# design.net
KiCad netlist of a schematic drawn in Altium Designer
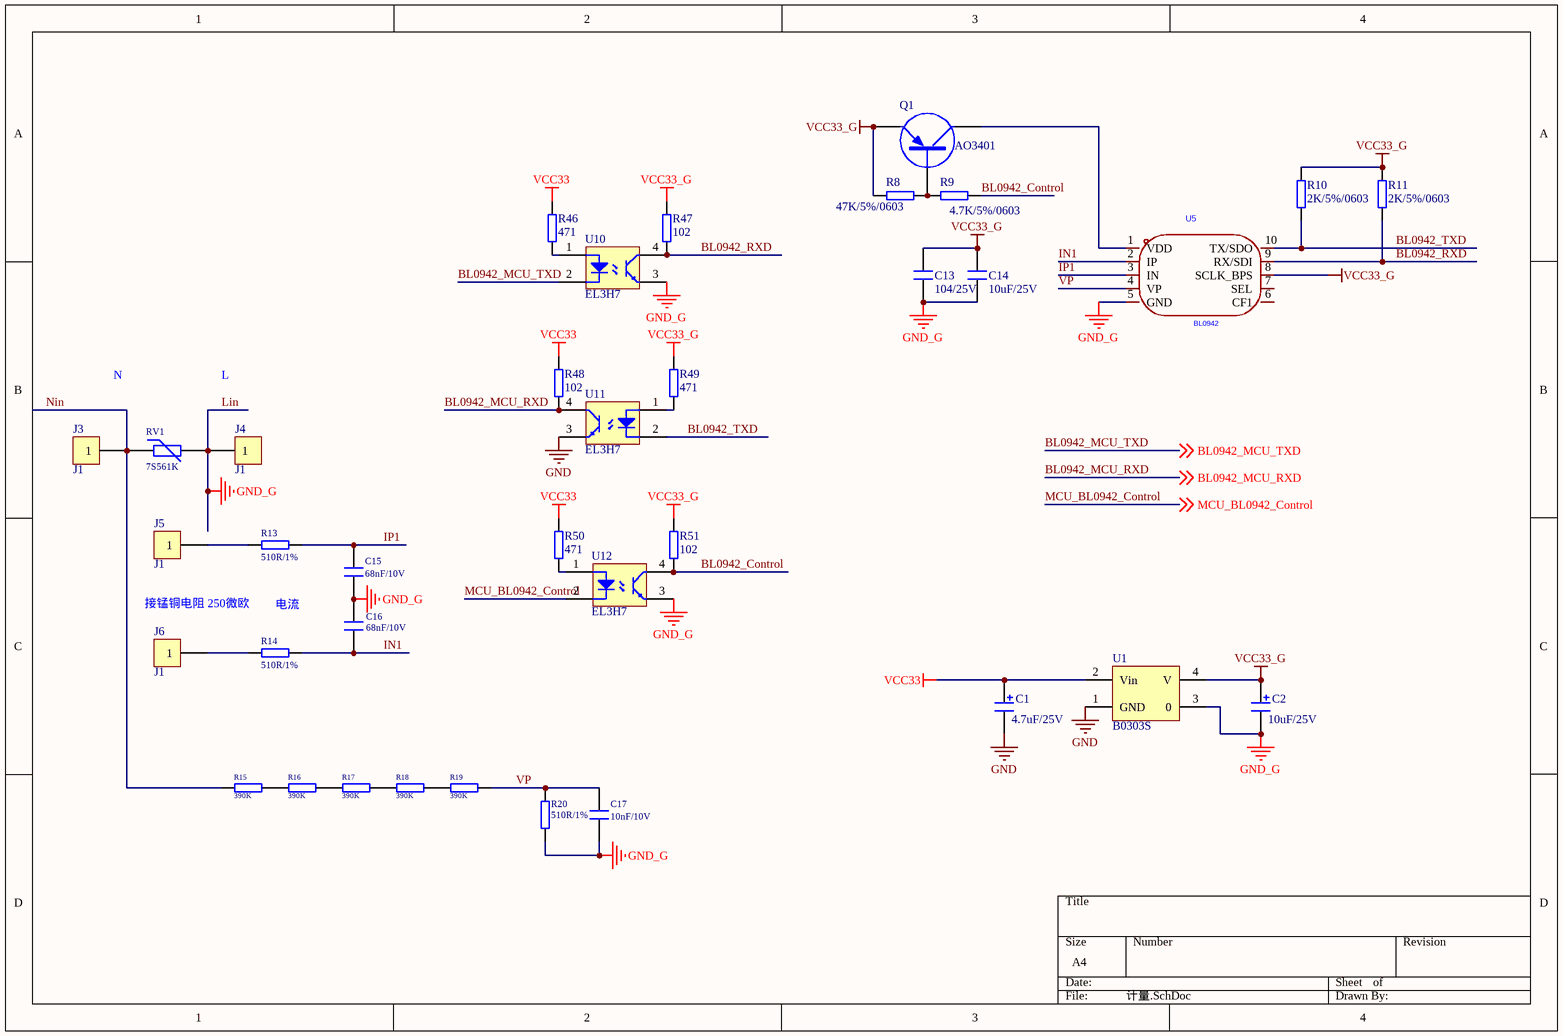
[diagram p0: 计量.SchDoc]

(export (version "E")
  (design (tool "Eeschema 10.0.6"))
  (components
    (comp (ref "C1") (value "4.7uF/25V") (footprint "0805R") (libsource (lib "ES_Schematic") (part "CAP+")))
    (comp (ref "C2") (value "10uF/25V") (footprint "0805R") (libsource (lib "ES_Schematic") (part "CAP+")))
    (comp (ref "C13") (value "104/25V") (footprint "0603R") (libsource (lib "ES_Schematic") (part "CAP_1")))
    (comp (ref "C14") (value "10uF/25V") (footprint "0603R") (libsource (lib "ES_Schematic") (part "CAP_1")))
    (comp (ref "C15") (value "68nF/10V") (footprint "0603R") (libsource (lib "ES_Schematic") (part "CAP")))
    (comp (ref "C16") (value "68nF/10V") (footprint "0603R") (libsource (lib "ES_Schematic") (part "CAP")))
    (comp (ref "C17") (value "10nF/10V") (footprint "0603R") (libsource (lib "ES_Schematic") (part "CAP")))
    (comp (ref "J3") (value "J1") (footprint "贴片焊盘V1（3*2椭圆）") (libsource (lib "ES_Schematic") (part "J1")))
    (comp (ref "J4") (value "J1") (footprint "贴片焊盘V1（3*2椭圆）") (libsource (lib "") (part "J1_1")))
    (comp (ref "J5") (value "J1") (footprint "贴片焊盘V1（3*2椭圆）") (libsource (lib "ES_Schematic") (part "J1")))
    (comp (ref "J6") (value "J1") (footprint "贴片焊盘V1（3*2椭圆）") (libsource (lib "ES_Schematic") (part "J1")))
    (comp (ref "Q1") (value "AO3401") (footprint "SOT-23") (libsource (lib "ES_Schematic") (part "PNP")))
    (comp (ref "R8") (value "47K/5%/0603") (footprint "0603R") (libsource (lib "ES_Schematic") (part "RES")))
    (comp (ref "R9") (value "4.7K/5%/0603") (footprint "0603R") (libsource (lib "ES_Schematic") (part "RES")))
    (comp (ref "R10") (value "2K/5%/0603") (footprint "0603R") (libsource (lib "ES_Schematic") (part "RES")))
    (comp (ref "R11") (value "2K/5%/0603") (footprint "0603R") (libsource (lib "ES_Schematic") (part "RES")))
    (comp (ref "R13") (value "510R/1%") (footprint "0603R") (libsource (lib "ES_Schematic") (part "RES")))
    (comp (ref "R14") (value "510R/1%") (footprint "0603R") (libsource (lib "ES_Schematic") (part "RES")))
    (comp (ref "R15") (value "390K") (footprint "0805R") (libsource (lib "ES_Schematic") (part "RES")))
    (comp (ref "R16") (value "390K") (footprint "0805R") (libsource (lib "ES_Schematic") (part "RES")))
    (comp (ref "R17") (value "390K") (footprint "0805R") (libsource (lib "ES_Schematic") (part "RES")))
    (comp (ref "R18") (value "390K") (footprint "0805R") (libsource (lib "ES_Schematic") (part "RES")))
    (comp (ref "R19") (value "390K") (footprint "0805R") (libsource (lib "ES_Schematic") (part "RES")))
    (comp (ref "R20") (value "510R/1%") (footprint "0603R") (libsource (lib "ES_Schematic") (part "RES")))
    (comp (ref "R46") (value "471") (footprint "0603R") (libsource (lib "ES_Schematic") (part "RES")))
    (comp (ref "R47") (value "102") (footprint "0603R") (libsource (lib "ES_Schematic") (part "RES")))
    (comp (ref "R48") (value "102") (footprint "0603R") (libsource (lib "ES_Schematic") (part "RES")))
    (comp (ref "R49") (value "471") (footprint "0603R") (libsource (lib "ES_Schematic") (part "RES")))
    (comp (ref "R50") (value "471") (footprint "0603R") (libsource (lib "ES_Schematic") (part "RES")))
    (comp (ref "R51") (value "102") (footprint "0603R") (libsource (lib "ES_Schematic") (part "RES")))
    (comp (ref "RV1")
      (value "7S561K")
      (footprint "10D821K")
      (description "Varistor (Voltage-Sensitive Resistor)")
      (fields (field (name "PUBLISHER") "Altium Limited"))
      (libsource (lib "Miscellaneous Devices") (part "Res Varistor"))
    )
    (comp (ref "U1") (value "B0303S") (footprint "B1205S-1WR3") (libsource (lib "sangjian") (part "B0505S")))
    (comp (ref "U5")
      (value "BL0942")
      (footprint "BL0942-10pin")
      (fields (field (name "MANUFACTURER") "BL(上海贝岭)"))
      (libsource (lib "altium-import") (part "root_0_BL0942_C2837510_"))
    )
    (comp (ref "U10")
      (value "EL3H7")
      (footprint "EL3H7")
      (libsource (lib "ES_Schematic") (part "Optical_Coupler_1"))
    )
    (comp (ref "U11") (value "EL3H7") (footprint "EL3H7") (libsource (lib "") (part "Optical_Coupler_1_1")))
    (comp (ref "U12")
      (value "EL3H7")
      (footprint "EL3H7")
      (libsource (lib "ES_Schematic") (part "Optical_Coupler_1"))
    )
  )
  (nets
    (net (code "1") (name "/BL0942_Control") (class "Default")
      (node (ref "R51") (pin "1") (pinfunction "1_1") (pintype "passive"))
      (node (ref "R9") (pin "2") (pinfunction "2_2") (pintype "passive"))
      (node (ref "U12") (pin "4") (pinfunction "C_4") (pintype "passive"))
    )
    (net (code "2") (name "/BL0942_RXD") (class "Default")
      (node (ref "R11") (pin "1") (pinfunction "1_1") (pintype "passive"))
      (node (ref "R47") (pin "1") (pinfunction "1_1") (pintype "passive"))
      (node (ref "U10") (pin "4") (pinfunction "C_4") (pintype "passive"))
      (node (ref "U5") (pin "9") (pinfunction "RX/SDI_9") (pintype "passive"))
    )
    (net (code "3") (name "/BL0942_TXD") (class "Default")
      (node (ref "R10") (pin "1") (pinfunction "1_1") (pintype "passive"))
      (node (ref "U11") (pin "2") (pinfunction "K_2") (pintype "passive"))
      (node (ref "U5") (pin "10") (pinfunction "TX/SDO_10") (pintype "passive"))
    )
    (net (code "4") (name "/IN1") (class "Default")
      (node (ref "C16") (pin "1") (pinfunction "1_1") (pintype "passive"))
      (node (ref "R14") (pin "2") (pinfunction "2_2") (pintype "passive"))
      (node (ref "U5") (pin "2") (pinfunction "IP_2") (pintype "passive"))
    )
    (net (code "5") (name "/IP1") (class "Default")
      (node (ref "C15") (pin "1") (pinfunction "1_1") (pintype "passive"))
      (node (ref "R13") (pin "2") (pinfunction "2_2") (pintype "passive"))
      (node (ref "U5") (pin "3") (pinfunction "IN_3") (pintype "passive"))
    )
    (net (code "6") (name "/Nin") (class "Default")
      (node (ref "J3") (pin "1") (pinfunction "1_1") (pintype "passive"))
      (node (ref "R15") (pin "2") (pinfunction "2_2") (pintype "passive"))
      (node (ref "RV1") (pin "1") (pinfunction "1_1") (pintype "passive"))
    )
    (net (code "7") (name "/VP") (class "Default")
      (node (ref "C17") (pin "1") (pinfunction "1_1") (pintype "passive"))
      (node (ref "R19") (pin "1") (pinfunction "1_1") (pintype "passive"))
      (node (ref "R20") (pin "2") (pinfunction "2_2") (pintype "passive"))
      (node (ref "U5") (pin "4") (pinfunction "VP_4") (pintype "passive"))
    )
    (net (code "8") (name "BL0942_MCU_RXD") (class "Default")
      (node (ref "R48") (pin "1") (pinfunction "1_1") (pintype "passive"))
      (node (ref "U11") (pin "4") (pinfunction "C_4") (pintype "passive"))
    )
    (net (code "9") (name "BL0942_MCU_TXD") (class "Default")
      (node (ref "U10") (pin "2") (pinfunction "K_2") (pintype "passive"))
    )
    (net (code "10") (name "GND") (class "Default")
      (node (ref "C1") (pin "2") (pinfunction "2_2") (pintype "passive"))
      (node (ref "U1") (pin "1") (pinfunction "GND_1") (pintype "passive"))
      (node (ref "U11") (pin "3") (pinfunction "E_3") (pintype "passive"))
    )
    (net (code "11") (name "GND_G") (class "Default")
      (node (ref "C13") (pin "1") (pinfunction "1_1") (pintype "passive"))
      (node (ref "C14") (pin "1") (pinfunction "1_1") (pintype "passive"))
      (node (ref "C15") (pin "2") (pinfunction "2_2") (pintype "passive"))
      (node (ref "C16") (pin "2") (pinfunction "2_2") (pintype "passive"))
      (node (ref "C17") (pin "2") (pinfunction "2_2") (pintype "passive"))
      (node (ref "C2") (pin "2") (pinfunction "2_2") (pintype "passive"))
      (node (ref "J4") (pin "1") (pinfunction "1_1") (pintype "passive"))
      (node (ref "R20") (pin "1") (pinfunction "1_1") (pintype "passive"))
      (node (ref "RV1") (pin "2") (pinfunction "2_2") (pintype "passive"))
      (node (ref "U1") (pin "3") (pinfunction "0_3") (pintype "passive"))
      (node (ref "U10") (pin "3") (pinfunction "E_3") (pintype "passive"))
      (node (ref "U12") (pin "3") (pinfunction "E_3") (pintype "passive"))
      (node (ref "U5") (pin "5") (pinfunction "GND_5") (pintype "passive"))
    )
    (net (code "12") (name "MCU_BL0942_Control") (class "Default")
      (node (ref "U12") (pin "2") (pinfunction "K_2") (pintype "passive"))
    )
    (net (code "13") (name "Net-(J5-Pad1)") (class "Default")
      (node (ref "J5") (pin "1") (pinfunction "1_1") (pintype "passive"))
      (node (ref "R13") (pin "1") (pinfunction "1_1") (pintype "passive"))
    )
    (net (code "14") (name "Net-(J6-Pad1)") (class "Default")
      (node (ref "J6") (pin "1") (pinfunction "1_1") (pintype "passive"))
      (node (ref "R14") (pin "1") (pinfunction "1_1") (pintype "passive"))
    )
    (net (code "15") (name "Net-(Q1-B)") (class "Default")
      (node (ref "Q1") (pin "1") (pinfunction "B_1") (pintype "passive"))
      (node (ref "R8") (pin "1") (pinfunction "1_1") (pintype "passive"))
      (node (ref "R9") (pin "1") (pinfunction "1_1") (pintype "passive"))
    )
    (net (code "16") (name "Net-(Q1-C)") (class "Default")
      (node (ref "Q1") (pin "3") (pinfunction "C_3") (pintype "passive"))
      (node (ref "U5") (pin "1") (pinfunction "VDD_1") (pintype "passive"))
    )
    (net (code "17") (name "Net-(R15-Pad1)") (class "Default")
      (node (ref "R15") (pin "1") (pinfunction "1_1") (pintype "passive"))
      (node (ref "R16") (pin "2") (pinfunction "2_2") (pintype "passive"))
    )
    (net (code "18") (name "Net-(R16-Pad1)") (class "Default")
      (node (ref "R16") (pin "1") (pinfunction "1_1") (pintype "passive"))
      (node (ref "R17") (pin "2") (pinfunction "2_2") (pintype "passive"))
    )
    (net (code "19") (name "Net-(R17-Pad1)") (class "Default")
      (node (ref "R17") (pin "1") (pinfunction "1_1") (pintype "passive"))
      (node (ref "R18") (pin "2") (pinfunction "2_2") (pintype "passive"))
    )
    (net (code "20") (name "Net-(R18-Pad1)") (class "Default")
      (node (ref "R18") (pin "1") (pinfunction "1_1") (pintype "passive"))
      (node (ref "R19") (pin "2") (pinfunction "2_2") (pintype "passive"))
    )
    (net (code "21") (name "Net-(U10-A)") (class "Default")
      (node (ref "R46") (pin "2") (pinfunction "2_2") (pintype "passive"))
      (node (ref "U10") (pin "1") (pinfunction "A_1") (pintype "passive"))
    )
    (net (code "22") (name "Net-(U11-A)") (class "Default")
      (node (ref "R49") (pin "2") (pinfunction "2_2") (pintype "passive"))
      (node (ref "U11") (pin "1") (pinfunction "A_1") (pintype "passive"))
    )
    (net (code "23") (name "Net-(U12-A)") (class "Default")
      (node (ref "R50") (pin "2") (pinfunction "2_2") (pintype "passive"))
      (node (ref "U12") (pin "1") (pinfunction "A_1") (pintype "passive"))
    )
    (net (code "24") (name "VCC33") (class "Default")
      (node (ref "C1") (pin "1") (pinfunction "1_1") (pintype "passive"))
      (node (ref "R46") (pin "1") (pinfunction "1_1") (pintype "passive"))
      (node (ref "R48") (pin "2") (pinfunction "2_2") (pintype "passive"))
      (node (ref "R50") (pin "1") (pinfunction "1_1") (pintype "passive"))
      (node (ref "U1") (pin "2") (pinfunction "Vin_2") (pintype "passive"))
    )
    (net (code "25") (name "VCC33_G") (class "Default")
      (node (ref "C13") (pin "2") (pinfunction "2_2") (pintype "passive"))
      (node (ref "C14") (pin "2") (pinfunction "2_2") (pintype "passive"))
      (node (ref "C2") (pin "1") (pinfunction "1_1") (pintype "passive"))
      (node (ref "Q1") (pin "2") (pinfunction "E_2") (pintype "passive"))
      (node (ref "R10") (pin "2") (pinfunction "2_2") (pintype "passive"))
      (node (ref "R11") (pin "2") (pinfunction "2_2") (pintype "passive"))
      (node (ref "R47") (pin "2") (pinfunction "2_2") (pintype "passive"))
      (node (ref "R49") (pin "1") (pinfunction "1_1") (pintype "passive"))
      (node (ref "R51") (pin "2") (pinfunction "2_2") (pintype "passive"))
      (node (ref "R8") (pin "2") (pinfunction "2_2") (pintype "passive"))
      (node (ref "U1") (pin "4") (pinfunction "V_4") (pintype "passive"))
      (node (ref "U5") (pin "8") (pinfunction "SCLK_BPS_8") (pintype "passive"))
    )
    (net (code "26") (name "unconnected-(U5-CF1-Pad6)") (class "Default")
      (node (ref "U5") (pin "6") (pinfunction "CF1_6") (pintype "passive"))
    )
    (net (code "27") (name "unconnected-(U5-SEL-Pad7)") (class "Default")
      (node (ref "U5") (pin "7") (pinfunction "SEL_7") (pintype "passive"))
    )
  )
)
